# 4_connection.net
KiCad netlist of a schematic drawn in Altium Designer
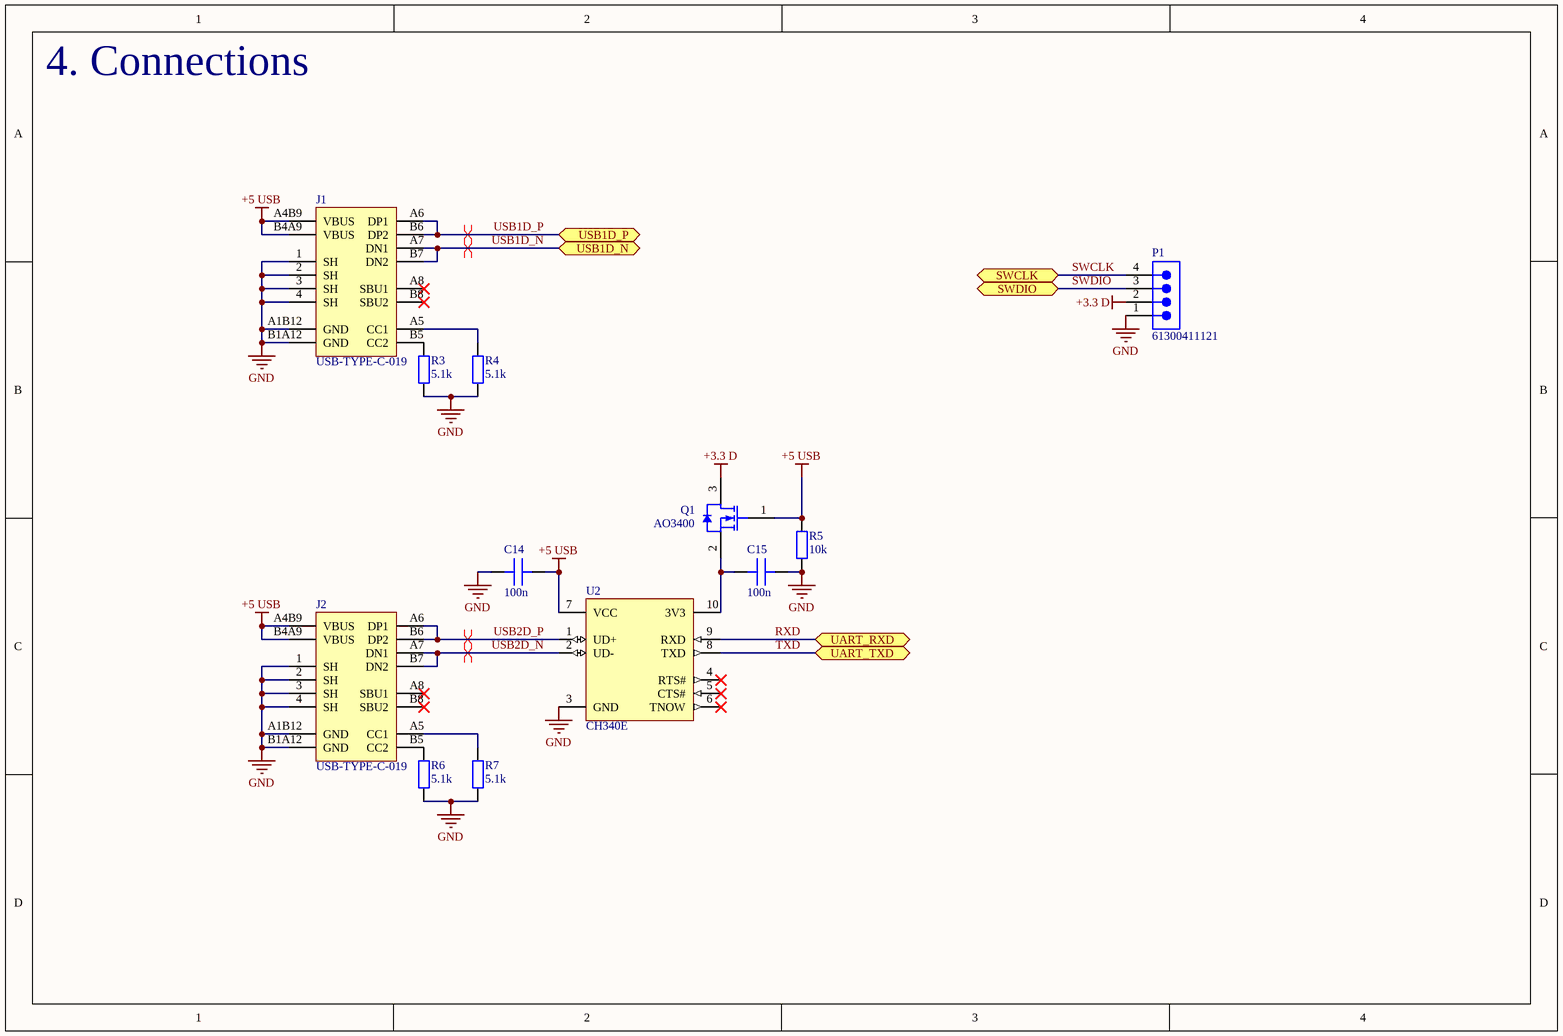
[diagram p0: 4_connection.SchDoc]

(export (version "E")
  (design (tool "Eeschema 10.0.6"))
  (components
    (comp (ref "C14")
      (value "100n")
      (footprint "IPC C C0402 NO SILK")
      (libsource (lib "JLCPCB Library") (part "Generic CAP 0402"))
    )
    (comp (ref "C15")
      (value "100n")
      (footprint "IPC C C0402 NO SILK")
      (libsource (lib "JLCPCB Library") (part "Generic CAP 0402"))
    )
    (comp (ref "J1")
      (value "USB-TYPE-C-019")
      (footprint "USB-TYPE-C-12+4P")
      (fields (field (name "MANUFACTURER") "DEALON(德艺隆)"))
      (libsource (lib "JLCPCB Library") (part "USB-TYPE-C-019"))
    )
    (comp (ref "J2")
      (value "USB-TYPE-C-019")
      (footprint "USB-TYPE-C-12+4P")
      (fields (field (name "MANUFACTURER") "DEALON(德艺隆)"))
      (libsource (lib "JLCPCB Library") (part "USB-TYPE-C-019"))
    )
    (comp (ref "P1")
      (value "61300411121")
      (footprint "61300411121")
      (libsource (lib "Altium Content Vault") (part "Header_Male_1R_04P"))
    )
    (comp (ref "Q1")
      (value "AO3400")
      (footprint "AO-SOT23-3_V")
      (description "N-channel Enhancement Mode Field-Effect Transistor; 5.8A/30V")
      (fields (field (name "MANUFACTURER") "Alpha and Omega"))
      (libsource (lib "Altium Content Vault") (part "AO-NEMOS-G1S2D3-3"))
    )
    (comp (ref "R3")
      (value "5.1k")
      (footprint "IPC C R0402 NO SILK")
      (libsource (lib "JLCPCB Library") (part "Generic RES 0402"))
    )
    (comp (ref "R4")
      (value "5.1k")
      (footprint "IPC C R0402 NO SILK")
      (libsource (lib "JLCPCB Library") (part "Generic RES 0402"))
    )
    (comp (ref "R5")
      (value "10k")
      (footprint "IPC C R0402 NO SILK")
      (libsource (lib "JLCPCB Library") (part "Generic RES 0402"))
    )
    (comp (ref "R6")
      (value "5.1k")
      (footprint "IPC C R0402 NO SILK")
      (libsource (lib "JLCPCB Library") (part "Generic RES 0402"))
    )
    (comp (ref "R7")
      (value "5.1k")
      (footprint "IPC C R0402 NO SILK")
      (libsource (lib "JLCPCB Library") (part "Generic RES 0402"))
    )
    (comp (ref "U2")
      (value "CH340E")
      (footprint "MSOP-UN10_L")
      (libsource (lib "JLCPCB Library") (part "CH340E"))
    )
  )
  (nets
    (net (code "1") (name "+3.3 D") (class "Default")
      (node (ref "P1") (pin "2") (pinfunction "2_2") (pintype "passive"))
      (node (ref "Q1") (pin "3") (pinfunction "D_3") (pintype "passive"))
    )
    (net (code "2") (name "+5 USB") (class "Default")
      (node (ref "C14") (pin "2") (pinfunction "2_2") (pintype "passive"))
      (node (ref "J1") (pin "A4B9") (pinfunction "VBUS_A4B9") (pintype "power_in"))
      (node (ref "J1") (pin "B4A9") (pinfunction "VBUS_B4A9") (pintype "power_in"))
      (node (ref "J2") (pin "A4B9") (pinfunction "VBUS_A4B9") (pintype "power_in"))
      (node (ref "J2") (pin "B4A9") (pinfunction "VBUS_B4A9") (pintype "power_in"))
      (node (ref "Q1") (pin "1") (pinfunction "G_1") (pintype "passive"))
      (node (ref "R5") (pin "2") (pinfunction "2_2") (pintype "passive"))
      (node (ref "U2") (pin "7") (pinfunction "VCC_7") (pintype "power_in"))
    )
    (net (code "3") (name "/RXD") (class "Default")
      (node (ref "U2") (pin "9") (pinfunction "RXD_9") (pintype "input"))
    )
    (net (code "4") (name "/SWCLK") (class "Default")
      (node (ref "P1") (pin "4") (pinfunction "4_4") (pintype "passive"))
    )
    (net (code "5") (name "/SWDIO") (class "Default")
      (node (ref "P1") (pin "3") (pinfunction "3_3") (pintype "passive"))
    )
    (net (code "6") (name "/TXD") (class "Default")
      (node (ref "U2") (pin "8") (pinfunction "TXD_8") (pintype "output"))
    )
    (net (code "7") (name "/USB1D_N") (class "Default")
      (node (ref "J1") (pin "A7") (pinfunction "DN1_A7") (pintype "passive"))
      (node (ref "J1") (pin "B7") (pinfunction "DN2_B7") (pintype "passive"))
    )
    (net (code "8") (name "/USB1D_P") (class "Default")
      (node (ref "J1") (pin "A6") (pinfunction "DP1_A6") (pintype "passive"))
      (node (ref "J1") (pin "B6") (pinfunction "DP2_B6") (pintype "passive"))
    )
    (net (code "9") (name "/USB2D_N") (class "Default")
      (node (ref "J2") (pin "A7") (pinfunction "DN1_A7") (pintype "passive"))
      (node (ref "J2") (pin "B7") (pinfunction "DN2_B7") (pintype "passive"))
      (node (ref "U2") (pin "2") (pinfunction "UD-_2") (pintype "bidirectional"))
    )
    (net (code "10") (name "/USB2D_P") (class "Default")
      (node (ref "J2") (pin "A6") (pinfunction "DP1_A6") (pintype "passive"))
      (node (ref "J2") (pin "B6") (pinfunction "DP2_B6") (pintype "passive"))
      (node (ref "U2") (pin "1") (pinfunction "UD+_1") (pintype "bidirectional"))
    )
    (net (code "11") (name "GND") (class "Default")
      (node (ref "C14") (pin "1") (pinfunction "1_1") (pintype "passive"))
      (node (ref "C15") (pin "1") (pinfunction "1_1") (pintype "passive"))
      (node (ref "J1") (pin "1") (pinfunction "SH_1") (pintype "passive"))
      (node (ref "J1") (pin "2") (pinfunction "SH_2") (pintype "passive"))
      (node (ref "J1") (pin "3") (pinfunction "SH_3") (pintype "passive"))
      (node (ref "J1") (pin "4") (pinfunction "SH_4") (pintype "passive"))
      (node (ref "J1") (pin "A1B12") (pinfunction "GND_A1B12") (pintype "power_in"))
      (node (ref "J1") (pin "B1A12") (pinfunction "GND_B1A12") (pintype "power_in"))
      (node (ref "J2") (pin "1") (pinfunction "SH_1") (pintype "passive"))
      (node (ref "J2") (pin "2") (pinfunction "SH_2") (pintype "passive"))
      (node (ref "J2") (pin "3") (pinfunction "SH_3") (pintype "passive"))
      (node (ref "J2") (pin "4") (pinfunction "SH_4") (pintype "passive"))
      (node (ref "J2") (pin "A1B12") (pinfunction "GND_A1B12") (pintype "power_in"))
      (node (ref "J2") (pin "B1A12") (pinfunction "GND_B1A12") (pintype "power_in"))
      (node (ref "P1") (pin "1") (pinfunction "1_1") (pintype "passive"))
      (node (ref "R3") (pin "1") (pinfunction "1_1") (pintype "passive"))
      (node (ref "R4") (pin "1") (pinfunction "1_1") (pintype "passive"))
      (node (ref "R5") (pin "1") (pinfunction "1_1") (pintype "passive"))
      (node (ref "R6") (pin "1") (pinfunction "1_1") (pintype "passive"))
      (node (ref "R7") (pin "1") (pinfunction "1_1") (pintype "passive"))
      (node (ref "U2") (pin "3") (pinfunction "GND_3") (pintype "power_in"))
    )
    (net (code "12") (name "Net-(J1-CC1)") (class "Default")
      (node (ref "J1") (pin "A5") (pinfunction "CC1_A5") (pintype "passive"))
      (node (ref "R4") (pin "2") (pinfunction "2_2") (pintype "passive"))
    )
    (net (code "13") (name "Net-(J1-CC2)") (class "Default")
      (node (ref "J1") (pin "B5") (pinfunction "CC2_B5") (pintype "passive"))
      (node (ref "R3") (pin "2") (pinfunction "2_2") (pintype "passive"))
    )
    (net (code "14") (name "Net-(J2-CC1)") (class "Default")
      (node (ref "J2") (pin "A5") (pinfunction "CC1_A5") (pintype "passive"))
      (node (ref "R7") (pin "2") (pinfunction "2_2") (pintype "passive"))
    )
    (net (code "15") (name "Net-(J2-CC2)") (class "Default")
      (node (ref "J2") (pin "B5") (pinfunction "CC2_B5") (pintype "passive"))
      (node (ref "R6") (pin "2") (pinfunction "2_2") (pintype "passive"))
    )
    (net (code "16") (name "Net-(Q1-S)") (class "Default")
      (node (ref "C15") (pin "2") (pinfunction "2_2") (pintype "passive"))
      (node (ref "Q1") (pin "2") (pinfunction "S_2") (pintype "passive"))
      (node (ref "U2") (pin "10") (pinfunction "3V3_10") (pintype "power_in"))
    )
    (net (code "17") (name "unconnected-(J1-SBU1-PadA8)") (class "Default")
      (node (ref "J1") (pin "A8") (pinfunction "SBU1_A8") (pintype "passive+no_connect"))
    )
    (net (code "18") (name "unconnected-(J1-SBU2-PadB8)") (class "Default")
      (node (ref "J1") (pin "B8") (pinfunction "SBU2_B8") (pintype "passive+no_connect"))
    )
    (net (code "19") (name "unconnected-(J2-SBU1-PadA8)") (class "Default")
      (node (ref "J2") (pin "A8") (pinfunction "SBU1_A8") (pintype "passive+no_connect"))
    )
    (net (code "20") (name "unconnected-(J2-SBU2-PadB8)") (class "Default")
      (node (ref "J2") (pin "B8") (pinfunction "SBU2_B8") (pintype "passive+no_connect"))
    )
    (net (code "21") (name "unconnected-(U2-CTS#-Pad5)") (class "Default")
      (node (ref "U2") (pin "5") (pinfunction "CTS#_5") (pintype "input+no_connect"))
    )
    (net (code "22") (name "unconnected-(U2-RTS#-Pad4)") (class "Default")
      (node (ref "U2") (pin "4") (pinfunction "RTS#_4") (pintype "output+no_connect"))
    )
    (net (code "23") (name "unconnected-(U2-TNOW-Pad6)") (class "Default")
      (node (ref "U2") (pin "6") (pinfunction "TNOW_6") (pintype "output+no_connect"))
    )
  )
)
